# NodeSmartIrrigation.net
KiCad netlist of a schematic drawn in EAGLE
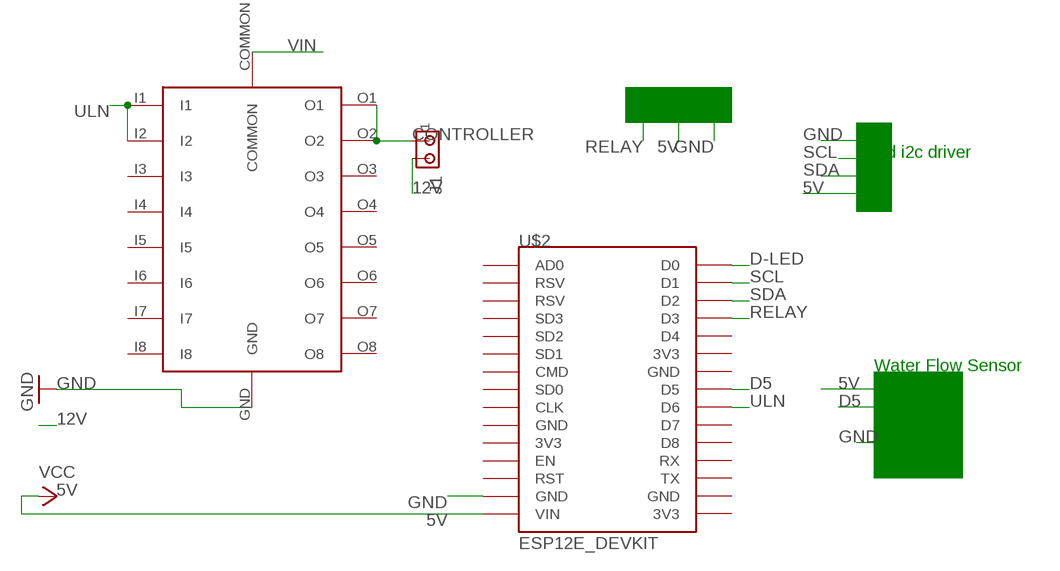
[diagram p0: schematic, sheet 1]

(export (version "E")
  (design (tool "Eeschema 10.0.6"))
  (components
    (comp (ref "J1")
      (value "MTA02-100")
      (footprint "eagle-import:10X02MTA")
      (libsource (lib "eagle-import") (part "MTA02-100"))
    )
    (comp (ref "U$1")
      (value "ULN2803AFWG")
      (footprint "eagle-import:ULN2803AFWG")
      (fields (field (name "MF") "Toshiba"))
      (libsource (lib "eagle-import") (part "ULN2803AFWG"))
    )
    (comp (ref "U$2")
      (value "ESP12E_DEVKIT")
      (footprint "eagle-import:ESP12E_DEVKIT")
      (libsource (lib "eagle-import") (part "ESP12E_DEVKIT"))
    )
  )
  (nets
    (net (code "1") (name "/12V") (class "Default")
      (node (ref "J1") (pin "2") (pinfunction "2_2") (pintype "passive"))
    )
    (net (code "2") (name "/CONTROLLER") (class "Default")
      (node (ref "J1") (pin "1") (pinfunction "1_1") (pintype "passive"))
      (node (ref "U$1") (pin "O1") (pinfunction "O1_O1") (pintype "bidirectional"))
      (node (ref "U$1") (pin "O2") (pinfunction "O2_O2") (pintype "bidirectional"))
    )
    (net (code "3") (name "/D-LED") (class "Default")
      (node (ref "U$2") (pin "D0") (pinfunction "D0_D0") (pintype "bidirectional"))
    )
    (net (code "4") (name "/D5") (class "Default")
      (node (ref "U$2") (pin "D5") (pinfunction "D5_D5") (pintype "bidirectional"))
    )
    (net (code "5") (name "/RELAY") (class "Default")
      (node (ref "U$2") (pin "D3") (pinfunction "D3_D3") (pintype "bidirectional"))
    )
    (net (code "6") (name "/SCL") (class "Default")
      (node (ref "U$2") (pin "D1") (pinfunction "D1_D1") (pintype "bidirectional"))
    )
    (net (code "7") (name "/SDA") (class "Default")
      (node (ref "U$2") (pin "D2") (pinfunction "D2_D2") (pintype "bidirectional"))
    )
    (net (code "8") (name "/ULN") (class "Default")
      (node (ref "U$1") (pin "I1") (pinfunction "I1_I1") (pintype "bidirectional"))
      (node (ref "U$1") (pin "I2") (pinfunction "I2_I2") (pintype "bidirectional"))
      (node (ref "U$2") (pin "D6") (pinfunction "D6_D6") (pintype "bidirectional"))
    )
    (net (code "9") (name "/VIN") (class "Default")
      (node (ref "U$1") (pin "COMMON") (pinfunction "COMMON_COMMON") (pintype "bidirectional"))
    )
    (net (code "10") (name "GND") (class "Default")
      (node (ref "U$1") (pin "GND") (pinfunction "GND_GND") (pintype "bidirectional"))
      (node (ref "U$2") (pin "GND@1") (pinfunction "GND_GND@1") (pintype "bidirectional"))
    )
    (net (code "11") (name "VCC") (class "Default")
      (node (ref "U$2") (pin "VIN") (pinfunction "VIN_VIN") (pintype "bidirectional"))
    )
    (net (code "12") (name "unconnected-(U$1-PadI3)") (class "Default")
      (node (ref "U$1") (pin "I3") (pinfunction "I3_I3") (pintype "bidirectional"))
    )
    (net (code "13") (name "unconnected-(U$1-PadI4)") (class "Default")
      (node (ref "U$1") (pin "I4") (pinfunction "I4_I4") (pintype "bidirectional"))
    )
    (net (code "14") (name "unconnected-(U$1-PadI5)") (class "Default")
      (node (ref "U$1") (pin "I5") (pinfunction "I5_I5") (pintype "bidirectional"))
    )
    (net (code "15") (name "unconnected-(U$1-PadI6)") (class "Default")
      (node (ref "U$1") (pin "I6") (pinfunction "I6_I6") (pintype "bidirectional"))
    )
    (net (code "16") (name "unconnected-(U$1-PadI7)") (class "Default")
      (node (ref "U$1") (pin "I7") (pinfunction "I7_I7") (pintype "bidirectional"))
    )
    (net (code "17") (name "unconnected-(U$1-PadI8)") (class "Default")
      (node (ref "U$1") (pin "I8") (pinfunction "I8_I8") (pintype "bidirectional"))
    )
    (net (code "18") (name "unconnected-(U$1-PadO3)") (class "Default")
      (node (ref "U$1") (pin "O3") (pinfunction "O3_O3") (pintype "bidirectional"))
    )
    (net (code "19") (name "unconnected-(U$1-PadO4)") (class "Default")
      (node (ref "U$1") (pin "O4") (pinfunction "O4_O4") (pintype "bidirectional"))
    )
    (net (code "20") (name "unconnected-(U$1-PadO5)") (class "Default")
      (node (ref "U$1") (pin "O5") (pinfunction "O5_O5") (pintype "bidirectional"))
    )
    (net (code "21") (name "unconnected-(U$1-PadO6)") (class "Default")
      (node (ref "U$1") (pin "O6") (pinfunction "O6_O6") (pintype "bidirectional"))
    )
    (net (code "22") (name "unconnected-(U$1-PadO7)") (class "Default")
      (node (ref "U$1") (pin "O7") (pinfunction "O7_O7") (pintype "bidirectional"))
    )
    (net (code "23") (name "unconnected-(U$1-PadO8)") (class "Default")
      (node (ref "U$1") (pin "O8") (pinfunction "O8_O8") (pintype "bidirectional"))
    )
    (net (code "24") (name "unconnected-(U$2-3V3-Pad3V3@0)") (class "Default")
      (node (ref "U$2") (pin "3V3@0") (pinfunction "3V3_3V3@0") (pintype "bidirectional"))
    )
    (net (code "25") (name "unconnected-(U$2-3V3-Pad3V3@1)") (class "Default")
      (node (ref "U$2") (pin "3V3@1") (pinfunction "3V3_3V3@1") (pintype "bidirectional"))
    )
    (net (code "26") (name "unconnected-(U$2-3V3-Pad3V3@2)") (class "Default")
      (node (ref "U$2") (pin "3V3@2") (pinfunction "3V3_3V3@2") (pintype "bidirectional"))
    )
    (net (code "27") (name "unconnected-(U$2-GND-PadGND@0)") (class "Default")
      (node (ref "U$2") (pin "GND@0") (pinfunction "GND_GND@0") (pintype "bidirectional"))
    )
    (net (code "28") (name "unconnected-(U$2-GND-PadGND@2)") (class "Default")
      (node (ref "U$2") (pin "GND@2") (pinfunction "GND_GND@2") (pintype "bidirectional"))
    )
    (net (code "29") (name "unconnected-(U$2-GND-PadGND@3)") (class "Default")
      (node (ref "U$2") (pin "GND@3") (pinfunction "GND_GND@3") (pintype "bidirectional"))
    )
    (net (code "30") (name "unconnected-(U$2-PadAD0)") (class "Default")
      (node (ref "U$2") (pin "AD0") (pinfunction "AD0_AD0") (pintype "bidirectional"))
    )
    (net (code "31") (name "unconnected-(U$2-PadCLK)") (class "Default")
      (node (ref "U$2") (pin "CLK") (pinfunction "CLK_CLK") (pintype "bidirectional"))
    )
    (net (code "32") (name "unconnected-(U$2-PadCMD)") (class "Default")
      (node (ref "U$2") (pin "CMD") (pinfunction "CMD_CMD") (pintype "bidirectional"))
    )
    (net (code "33") (name "unconnected-(U$2-PadD4)") (class "Default")
      (node (ref "U$2") (pin "D4") (pinfunction "D4_D4") (pintype "bidirectional"))
    )
    (net (code "34") (name "unconnected-(U$2-PadD7)") (class "Default")
      (node (ref "U$2") (pin "D7") (pinfunction "D7_D7") (pintype "bidirectional"))
    )
    (net (code "35") (name "unconnected-(U$2-PadD8)") (class "Default")
      (node (ref "U$2") (pin "D8") (pinfunction "D8_D8") (pintype "bidirectional"))
    )
    (net (code "36") (name "unconnected-(U$2-PadEN)") (class "Default")
      (node (ref "U$2") (pin "EN") (pinfunction "EN_EN") (pintype "bidirectional"))
    )
    (net (code "37") (name "unconnected-(U$2-PadRST)") (class "Default")
      (node (ref "U$2") (pin "RST") (pinfunction "RST_RST") (pintype "bidirectional"))
    )
    (net (code "38") (name "unconnected-(U$2-PadRX)") (class "Default")
      (node (ref "U$2") (pin "RX") (pinfunction "RX_RX") (pintype "bidirectional"))
    )
    (net (code "39") (name "unconnected-(U$2-PadSD0)") (class "Default")
      (node (ref "U$2") (pin "SD0") (pinfunction "SD0_SD0") (pintype "bidirectional"))
    )
    (net (code "40") (name "unconnected-(U$2-PadSD1)") (class "Default")
      (node (ref "U$2") (pin "SD1") (pinfunction "SD1_SD1") (pintype "bidirectional"))
    )
    (net (code "41") (name "unconnected-(U$2-PadSD2)") (class "Default")
      (node (ref "U$2") (pin "SD2") (pinfunction "SD2_SD2") (pintype "bidirectional"))
    )
    (net (code "42") (name "unconnected-(U$2-PadSD3)") (class "Default")
      (node (ref "U$2") (pin "SD3") (pinfunction "SD3_SD3") (pintype "bidirectional"))
    )
    (net (code "43") (name "unconnected-(U$2-PadTX)") (class "Default")
      (node (ref "U$2") (pin "TX") (pinfunction "TX_TX") (pintype "bidirectional"))
    )
    (net (code "44") (name "unconnected-(U$2-RSV-PadRSV@0)") (class "Default")
      (node (ref "U$2") (pin "RSV@0") (pinfunction "RSV_RSV@0") (pintype "bidirectional"))
    )
    (net (code "45") (name "unconnected-(U$2-RSV-PadRSV@1)") (class "Default")
      (node (ref "U$2") (pin "RSV@1") (pinfunction "RSV_RSV@1") (pintype "bidirectional"))
    )
  )
)
